# t10_programmin_adapter2.net
KiCad netlist of a schematic drawn in EAGLE
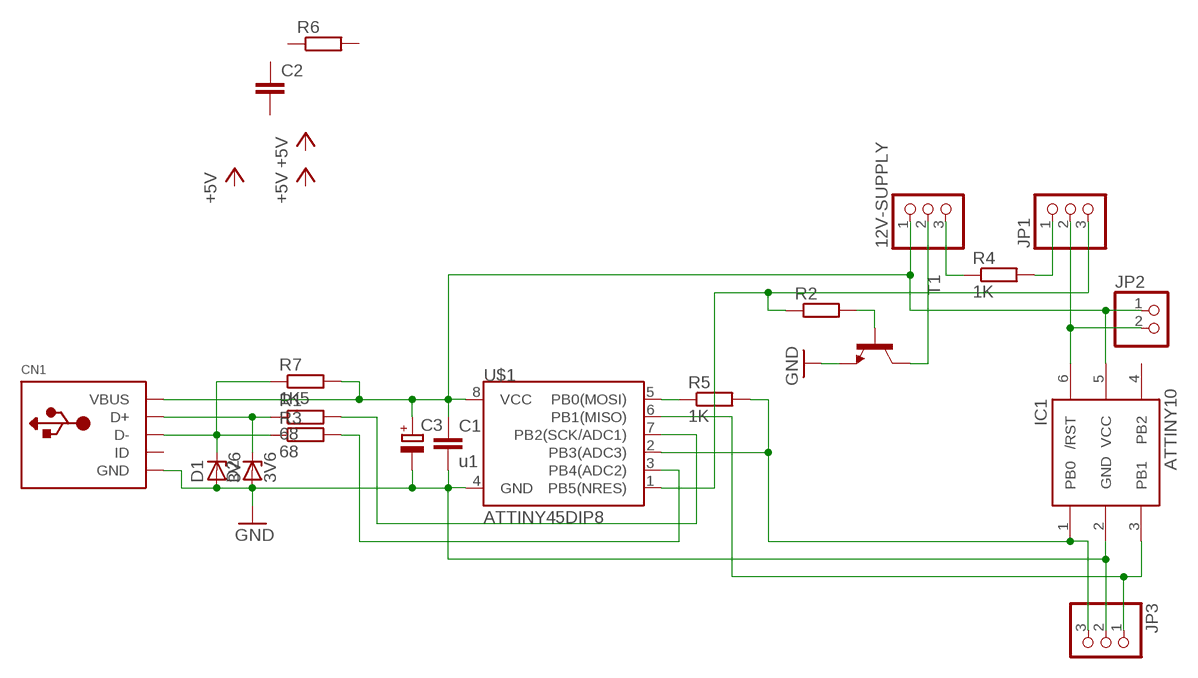
[diagram p0: schematic, sheet 1]

(export (version "E")
  (design (tool "Eeschema 10.0.6"))
  (components
    (comp (ref "12V-SUPPLY")
      (value "PINHD-1X3/90")
      (footprint "eagle-import:1X03_90")
      (libsource (lib "eagle-import") (part "PINHD-1X3/90"))
    )
    (comp (ref "C1")
      (value "u1")
      (footprint "eagle-import:C025-025X050")
      (libsource (lib "eagle-import") (part "C-EU025-025X050"))
    )
    (comp (ref "C2")
      (value "C-EU025-025X050")
      (footprint "eagle-import:C025-025X050")
      (libsource (lib "eagle-import") (part "C-EU025-025X050"))
    )
    (comp (ref "C3")
      (value "CPOL-EUE2.5-6")
      (footprint "eagle-import:E2,5-6")
      (libsource (lib "eagle-import") (part "CPOL-EUE2.5-6"))
    )
    (comp (ref "CN1")
      (value "USBTHM")
      (footprint "eagle-import:USB-MINIB-THM")
      (libsource (lib "eagle-import") (part "USBTHM"))
    )
    (comp (ref "D1")
      (value "3V6")
      (footprint "eagle-import:ZDIO-7.5")
      (libsource (lib "eagle-import") (part "ZENER-DIODEZD-7.5"))
    )
    (comp (ref "D2")
      (value "3V6")
      (footprint "eagle-import:ZDIO-2.5")
      (libsource (lib "eagle-import") (part "ZENER-DIODEZD-2.5"))
    )
    (comp (ref "IC1")
      (value "ATTINY10")
      (footprint "eagle-import:SOT23-6")
      (libsource (lib "eagle-import") (part "ATTINY10"))
    )
    (comp (ref "JP1")
      (value "PINHD-1X3")
      (footprint "eagle-import:1X03")
      (libsource (lib "eagle-import") (part "PINHD-1X3"))
    )
    (comp (ref "JP2")
      (value "PINHD-1X2")
      (footprint "eagle-import:1X02")
      (libsource (lib "eagle-import") (part "PINHD-1X2"))
    )
    (comp (ref "JP3")
      (value "PINHD-1X3")
      (footprint "eagle-import:1X03")
      (libsource (lib "eagle-import") (part "PINHD-1X3"))
    )
    (comp (ref "R1")
      (value "68")
      (footprint "eagle-import:0204_7")
      (libsource (lib "eagle-import") (part "R-EU_0204/7"))
    )
    (comp (ref "R2")
      (value "R-EU_0207/10")
      (footprint "eagle-import:0207_10")
      (libsource (lib "eagle-import") (part "R-EU_0207/10"))
    )
    (comp (ref "R3")
      (value "68")
      (footprint "eagle-import:0207_2V")
      (libsource (lib "eagle-import") (part "R-EU_0207/2V"))
    )
    (comp (ref "R4")
      (value "1K")
      (footprint "eagle-import:0207_2V")
      (libsource (lib "eagle-import") (part "R-EU_0207/2V"))
    )
    (comp (ref "R5")
      (value "1K")
      (footprint "eagle-import:0204_7")
      (libsource (lib "eagle-import") (part "R-EU_0204/7"))
    )
    (comp (ref "R6")
      (value "R-EU_0207/2V")
      (footprint "eagle-import:0207_2V")
      (libsource (lib "eagle-import") (part "R-EU_0207/2V"))
    )
    (comp (ref "R7")
      (value "1K5")
      (footprint "eagle-import:0207_2V")
      (libsource (lib "eagle-import") (part "R-EU_0207/2V"))
    )
    (comp (ref "T1")
      (value "-NPN-TO92-EBC")
      (footprint "eagle-import:TO92-EBC")
      (libsource (lib "eagle-import") (part "-NPN-TO92-EBC"))
    )
    (comp (ref "U$1")
      (value "ATTINY45DIP8")
      (footprint "eagle-import:DIP08")
      (libsource (lib "eagle-import") (part "ATTINY45DIP8"))
    )
  )
  (nets
    (net (code "2") (name "GND") (class "Default")
      (node (ref "C1") (pin "2") (pinfunction "2_2") (pintype "passive"))
      (node (ref "C3") (pin "-") (pinfunction "-_-") (pintype "passive"))
      (node (ref "CN1") (pin "GND") (pinfunction "GND_GND") (pintype "power_in"))
      (node (ref "D1") (pin "A") (pinfunction "A_A") (pintype "passive"))
      (node (ref "D2") (pin "A") (pinfunction "A_A") (pintype "passive"))
      (node (ref "IC1") (pin "2") (pinfunction "GND_2") (pintype "power_in"))
      (node (ref "JP3") (pin "2") (pinfunction "2_2") (pintype "passive"))
      (node (ref "T1") (pin "E") (pinfunction "E_E") (pintype "passive"))
      (node (ref "U$1") (pin "4") (pinfunction "GND_4") (pintype "bidirectional"))
    )
    (net (code "3") (name "Net-(12V-SUPPLY-Pad2)") (class "Default")
      (node (ref "12V-SUPPLY") (pin "2") (pinfunction "2_2") (pintype "passive"))
      (node (ref "T1") (pin "C") (pinfunction "C_C") (pintype "passive"))
    )
    (net (code "4") (name "Net-(12V-SUPPLY-Pad3)") (class "Default")
      (node (ref "12V-SUPPLY") (pin "3") (pinfunction "3_3") (pintype "passive"))
      (node (ref "R4") (pin "1") (pinfunction "1_1") (pintype "passive"))
    )
    (net (code "5") (name "Net-(CN1-PadD+)") (class "Default")
      (node (ref "CN1") (pin "D+") (pinfunction "D+_D+") (pintype "bidirectional"))
      (node (ref "D2") (pin "C") (pinfunction "C_C") (pintype "passive"))
      (node (ref "R1") (pin "1") (pinfunction "1_1") (pintype "passive"))
    )
    (net (code "6") (name "Net-(CN1-PadD-)") (class "Default")
      (node (ref "CN1") (pin "D-") (pinfunction "D-_D-") (pintype "bidirectional"))
      (node (ref "D1") (pin "C") (pinfunction "C_C") (pintype "passive"))
      (node (ref "R3") (pin "1") (pinfunction "1_1") (pintype "passive"))
      (node (ref "R7") (pin "1") (pinfunction "1_1") (pintype "passive"))
    )
    (net (code "7") (name "Net-(IC1-PB0)") (class "Default")
      (node (ref "IC1") (pin "1") (pinfunction "PB0_1") (pintype "bidirectional"))
      (node (ref "JP3") (pin "3") (pinfunction "3_3") (pintype "passive"))
      (node (ref "R5") (pin "2") (pinfunction "2_2") (pintype "passive"))
      (node (ref "U$1") (pin "2") (pinfunction "PB3(ADC3)_2") (pintype "bidirectional"))
    )
    (net (code "8") (name "Net-(IC1-PB1)") (class "Default")
      (node (ref "IC1") (pin "3") (pinfunction "PB1_3") (pintype "bidirectional"))
      (node (ref "JP3") (pin "1") (pinfunction "1_1") (pintype "passive"))
      (node (ref "U$1") (pin "6") (pinfunction "PB1(MISO)_6") (pintype "bidirectional"))
    )
    (net (code "9") (name "Net-(IC1-VCC)") (class "Default")
      (node (ref "12V-SUPPLY") (pin "1") (pinfunction "1_1") (pintype "passive"))
      (node (ref "C1") (pin "1") (pinfunction "1_1") (pintype "passive"))
      (node (ref "C3") (pin "+") (pinfunction "+_+") (pintype "passive"))
      (node (ref "CN1") (pin "VBUS") (pinfunction "VBUS_VBUS") (pintype "power_in"))
      (node (ref "IC1") (pin "5") (pinfunction "VCC_5") (pintype "power_in"))
      (node (ref "JP2") (pin "1") (pinfunction "1_1") (pintype "passive"))
      (node (ref "R7") (pin "2") (pinfunction "2_2") (pintype "passive"))
      (node (ref "U$1") (pin "8") (pinfunction "VCC_8") (pintype "bidirectional"))
    )
    (net (code "10") (name "Net-(IC1-{slash}RST)") (class "Default")
      (node (ref "IC1") (pin "6") (pinfunction "/RST_6") (pintype "bidirectional"))
      (node (ref "JP1") (pin "2") (pinfunction "2_2") (pintype "passive"))
      (node (ref "JP2") (pin "2") (pinfunction "2_2") (pintype "passive"))
    )
    (net (code "11") (name "Net-(JP1-Pad1)") (class "Default")
      (node (ref "JP1") (pin "1") (pinfunction "1_1") (pintype "passive"))
      (node (ref "R4") (pin "2") (pinfunction "2_2") (pintype "passive"))
    )
    (net (code "12") (name "Net-(R2-Pad2)") (class "Default")
      (node (ref "R2") (pin "2") (pinfunction "2_2") (pintype "passive"))
      (node (ref "T1") (pin "B") (pinfunction "B_B") (pintype "passive"))
    )
    (net (code "13") (name "Net-(U$1-PB0(MOSI))") (class "Default")
      (node (ref "R5") (pin "1") (pinfunction "1_1") (pintype "passive"))
      (node (ref "U$1") (pin "5") (pinfunction "PB0(MOSI)_5") (pintype "bidirectional"))
    )
    (net (code "14") (name "Net-(U$1-PB2(SCK{slash}ADC1))") (class "Default")
      (node (ref "R1") (pin "2") (pinfunction "2_2") (pintype "passive"))
      (node (ref "U$1") (pin "7") (pinfunction "PB2(SCK/ADC1)_7") (pintype "bidirectional"))
    )
    (net (code "15") (name "Net-(U$1-PB4(ADC2))") (class "Default")
      (node (ref "R3") (pin "2") (pinfunction "2_2") (pintype "passive"))
      (node (ref "U$1") (pin "3") (pinfunction "PB4(ADC2)_3") (pintype "bidirectional"))
    )
    (net (code "16") (name "Net-(U$1-PB5(NRES))") (class "Default")
      (node (ref "JP1") (pin "3") (pinfunction "3_3") (pintype "passive"))
      (node (ref "R2") (pin "1") (pinfunction "1_1") (pintype "passive"))
      (node (ref "U$1") (pin "1") (pinfunction "PB5(NRES)_1") (pintype "bidirectional"))
    )
    (net (code "17") (name "unconnected-(C2-Pad1)") (class "Default")
      (node (ref "C2") (pin "1") (pinfunction "1_1") (pintype "passive"))
    )
    (net (code "18") (name "unconnected-(C2-Pad2)") (class "Default")
      (node (ref "C2") (pin "2") (pinfunction "2_2") (pintype "passive"))
    )
    (net (code "19") (name "unconnected-(CN1-PadID)") (class "Default")
      (node (ref "CN1") (pin "ID") (pinfunction "ID_ID") (pintype "bidirectional"))
    )
    (net (code "20") (name "unconnected-(IC1-PB2-Pad4)") (class "Default")
      (node (ref "IC1") (pin "4") (pinfunction "PB2_4") (pintype "bidirectional"))
    )
    (net (code "21") (name "unconnected-(R6-Pad1)") (class "Default")
      (node (ref "R6") (pin "1") (pinfunction "1_1") (pintype "passive"))
    )
    (net (code "22") (name "unconnected-(R6-Pad2)") (class "Default")
      (node (ref "R6") (pin "2") (pinfunction "2_2") (pintype "passive"))
    )
  )
)
